# ServoKnob.net
KiCad netlist of a schematic drawn in EAGLE
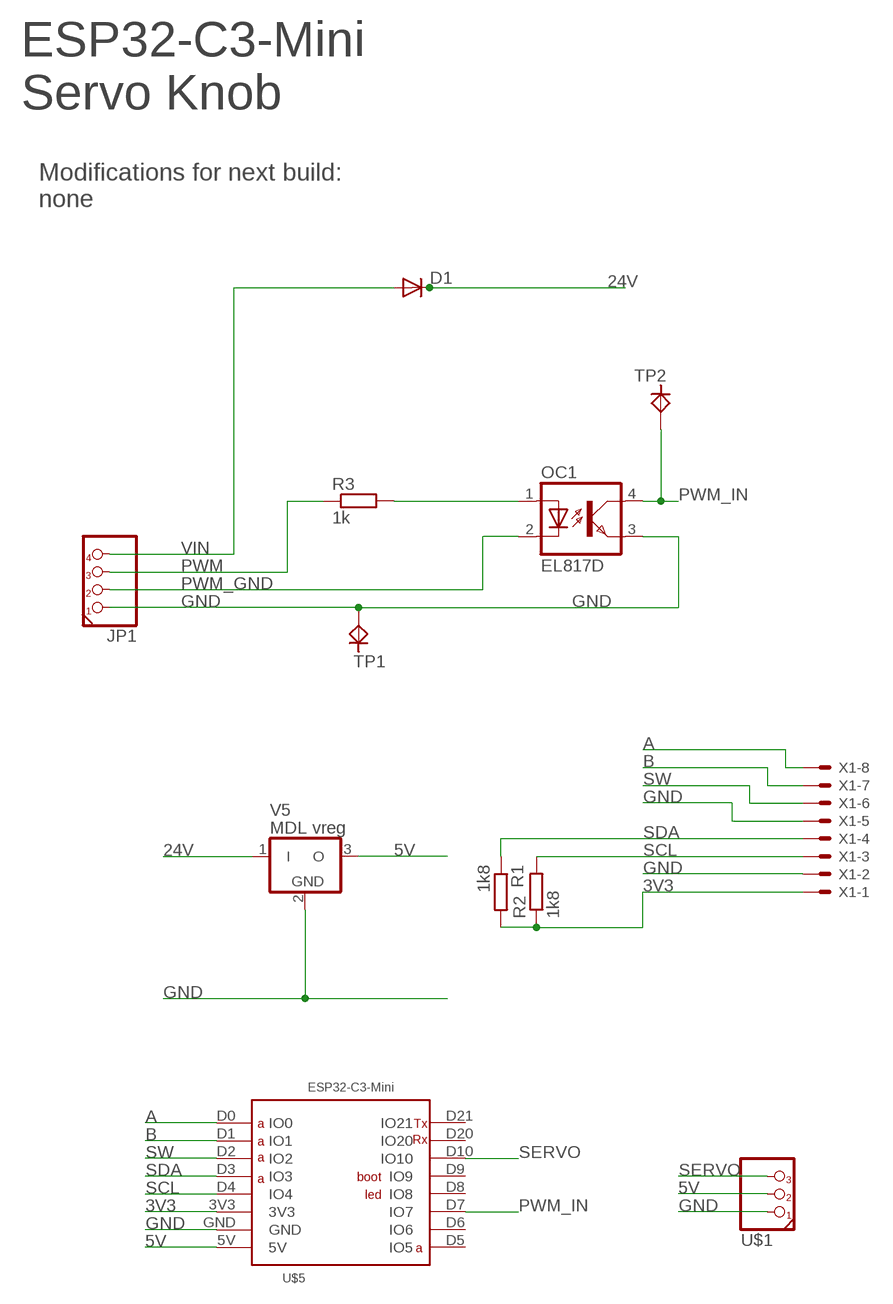
[diagram p0: schematic, sheet 1]

(export (version "E")
  (design (tool "Eeschema 10.0.6"))
  (components
    (comp (ref "D1")
      (value "DIODE-DO214ACI")
      (footprint "eagle-import:DO214ACI")
      (libsource (lib "eagle-import") (part "DIODE-DO214ACI"))
    )
    (comp (ref "JP1")
      (value "PINHD-1X4PH254")
      (footprint "eagle-import:1X04_PH254")
      (libsource (lib "eagle-import") (part "PINHD-1X4PH254"))
    )
    (comp (ref "OC1")
      (value "EL817D")
      (footprint "eagle-import:DIL04")
      (libsource (lib "eagle-import") (part "EL817D"))
    )
    (comp (ref "R1")
      (value "1k8")
      (footprint "eagle-import:R0805")
      (libsource (lib "eagle-import") (part "R-EU_R0805"))
    )
    (comp (ref "R2")
      (value "1k8")
      (footprint "eagle-import:R0805")
      (libsource (lib "eagle-import") (part "R-EU_R0805"))
    )
    (comp (ref "R3")
      (value "1k")
      (footprint "eagle-import:R0805")
      (libsource (lib "eagle-import") (part "R-EU_R0805"))
    )
    (comp (ref "TP1")
      (value "TESTPIN-TP10")
      (footprint "eagle-import:TP10")
      (libsource (lib "eagle-import") (part "TESTPIN-TP10"))
    )
    (comp (ref "TP2")
      (value "TESTPIN-TP10")
      (footprint "eagle-import:TP10")
      (libsource (lib "eagle-import") (part "TESTPIN-TP10"))
    )
    (comp (ref "U$1")
      (value "PINHD-1X3")
      (footprint "eagle-import:1X03")
      (libsource (lib "eagle-import") (part "PINHD-1X3"))
    )
    (comp (ref "U$5")
      (value "ESP32C3MINIL")
      (footprint "eagle-import:ESP32-C3-MINI")
      (libsource (lib "eagle-import") (part "ESP32C3MINIL"))
    )
    (comp (ref "V5")
      (value "MDL vreg")
      (footprint "eagle-import:MDLSTEPDOWNV02H")
      (libsource (lib "eagle-import") (part "VREGMDLSTDWNH"))
    )
    (comp (ref "X1")
      (value "JST-XH-08-PIN-L")
      (footprint "eagle-import:JST-XH-08-L")
      (libsource (lib "eagle-import") (part "JST-XH-08-PIN-L"))
    )
  )
  (nets
    (net (code "1") (name "/3V3") (class "Default")
      (node (ref "R1") (pin "2") (pinfunction "2_2") (pintype "passive"))
      (node (ref "R2") (pin "1") (pinfunction "1_1") (pintype "passive"))
      (node (ref "U$5") (pin "3V3") (pinfunction "3V3_3V3") (pintype "bidirectional"))
      (node (ref "X1") (pin "1") (pinfunction "S_1") (pintype "passive"))
    )
    (net (code "2") (name "/5V") (class "Default")
      (node (ref "U$1") (pin "2") (pinfunction "2_2") (pintype "passive"))
      (node (ref "U$5") (pin "5V") (pinfunction "5V_5V") (pintype "bidirectional"))
      (node (ref "V5") (pin "3") (pinfunction "O_3") (pintype "passive"))
    )
    (net (code "3") (name "/24V") (class "Default")
      (node (ref "D1") (pin "C") (pinfunction "C_C") (pintype "passive"))
      (node (ref "V5") (pin "1") (pinfunction "I_1") (pintype "input"))
    )
    (net (code "4") (name "/A") (class "Default")
      (node (ref "U$5") (pin "D0") (pinfunction "IO0_D0") (pintype "bidirectional"))
      (node (ref "X1") (pin "8") (pinfunction "S_8") (pintype "passive"))
    )
    (net (code "5") (name "/B") (class "Default")
      (node (ref "U$5") (pin "D1") (pinfunction "IO1_D1") (pintype "bidirectional"))
      (node (ref "X1") (pin "7") (pinfunction "S_7") (pintype "passive"))
    )
    (net (code "6") (name "/GND") (class "Default")
      (node (ref "JP1") (pin "1") (pinfunction "1_1") (pintype "passive"))
      (node (ref "OC1") (pin "3") (pinfunction "EMIT_3") (pintype "passive"))
      (node (ref "TP1") (pin "TP") (pinfunction "P$1_TP") (pintype "passive"))
      (node (ref "U$1") (pin "1") (pinfunction "1_1") (pintype "passive"))
      (node (ref "U$5") (pin "GND") (pinfunction "GND_GND") (pintype "bidirectional"))
      (node (ref "V5") (pin "2") (pinfunction "GND_2") (pintype "passive"))
      (node (ref "X1") (pin "2") (pinfunction "S_2") (pintype "passive"))
      (node (ref "X1") (pin "5") (pinfunction "S_5") (pintype "passive"))
    )
    (net (code "7") (name "/PWM") (class "Default")
      (node (ref "JP1") (pin "3") (pinfunction "3_3") (pintype "passive"))
      (node (ref "R3") (pin "1") (pinfunction "1_1") (pintype "passive"))
    )
    (net (code "8") (name "/PWM_GND") (class "Default")
      (node (ref "JP1") (pin "2") (pinfunction "2_2") (pintype "passive"))
      (node (ref "OC1") (pin "2") (pinfunction "C_2") (pintype "passive"))
    )
    (net (code "9") (name "/PWM_IN") (class "Default")
      (node (ref "OC1") (pin "4") (pinfunction "COL_4") (pintype "passive"))
      (node (ref "TP2") (pin "TP") (pinfunction "P$1_TP") (pintype "passive"))
      (node (ref "U$5") (pin "D7") (pinfunction "IO7_D7") (pintype "bidirectional"))
    )
    (net (code "10") (name "/SCL") (class "Default")
      (node (ref "R2") (pin "2") (pinfunction "2_2") (pintype "passive"))
      (node (ref "U$5") (pin "D4") (pinfunction "IO4_D4") (pintype "bidirectional"))
      (node (ref "X1") (pin "3") (pinfunction "S_3") (pintype "passive"))
    )
    (net (code "11") (name "/SDA") (class "Default")
      (node (ref "R1") (pin "1") (pinfunction "1_1") (pintype "passive"))
      (node (ref "U$5") (pin "D3") (pinfunction "IO3_D3") (pintype "bidirectional"))
      (node (ref "X1") (pin "4") (pinfunction "S_4") (pintype "passive"))
    )
    (net (code "12") (name "/SERVO") (class "Default")
      (node (ref "U$1") (pin "3") (pinfunction "3_3") (pintype "passive"))
      (node (ref "U$5") (pin "D10") (pinfunction "IO10_D10") (pintype "bidirectional"))
    )
    (net (code "13") (name "/SW") (class "Default")
      (node (ref "U$5") (pin "D2") (pinfunction "IO2_D2") (pintype "bidirectional"))
      (node (ref "X1") (pin "6") (pinfunction "S_6") (pintype "passive"))
    )
    (net (code "14") (name "/VIN") (class "Default")
      (node (ref "D1") (pin "A") (pinfunction "A_A") (pintype "passive"))
      (node (ref "JP1") (pin "4") (pinfunction "4_4") (pintype "passive"))
    )
    (net (code "15") (name "Net-(OC1-A)") (class "Default")
      (node (ref "OC1") (pin "1") (pinfunction "A_1") (pintype "passive"))
      (node (ref "R3") (pin "2") (pinfunction "2_2") (pintype "passive"))
    )
    (net (code "16") (name "unconnected-(U$5-IO5-PadD5)") (class "Default")
      (node (ref "U$5") (pin "D5") (pinfunction "IO5_D5") (pintype "bidirectional"))
    )
    (net (code "17") (name "unconnected-(U$5-IO6-PadD6)") (class "Default")
      (node (ref "U$5") (pin "D6") (pinfunction "IO6_D6") (pintype "bidirectional"))
    )
    (net (code "18") (name "unconnected-(U$5-IO8-PadD8)") (class "Default")
      (node (ref "U$5") (pin "D8") (pinfunction "IO8_D8") (pintype "bidirectional"))
    )
    (net (code "19") (name "unconnected-(U$5-IO9-PadD9)") (class "Default")
      (node (ref "U$5") (pin "D9") (pinfunction "IO9_D9") (pintype "bidirectional"))
    )
    (net (code "20") (name "unconnected-(U$5-IO20-PadD20)") (class "Default")
      (node (ref "U$5") (pin "D20") (pinfunction "IO20_D20") (pintype "bidirectional"))
    )
    (net (code "21") (name "unconnected-(U$5-IO21-PadD21)") (class "Default")
      (node (ref "U$5") (pin "D21") (pinfunction "IO21_D21") (pintype "bidirectional"))
    )
  )
)
